# RUMBA_TFT.net
KiCad netlist of a schematic drawn in Altium Designer
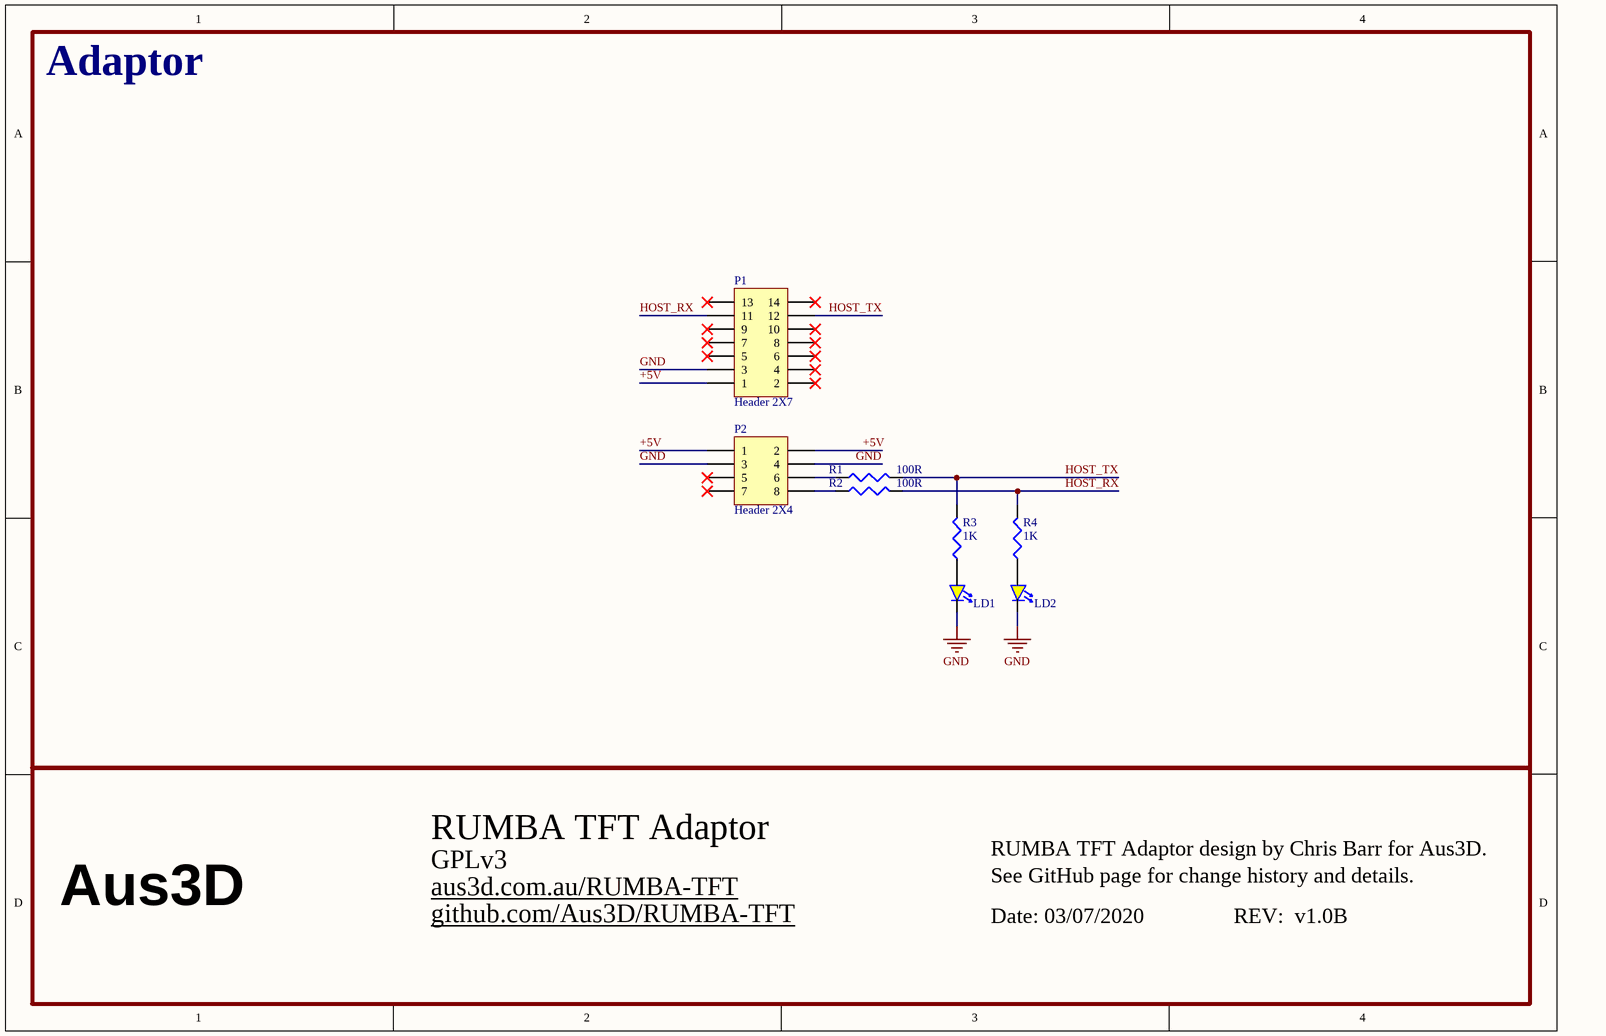
[diagram p0: RUMBA_TFT.SchDoc]

(export (version "E")
  (design (tool "Eeschema 10.0.6"))
  (components
    (comp (ref "LD1")
      (value "~")
      (footprint "LED 1608-0603")
      (description "LED YELLOW CLEAR CHIP SMD 0603")
      (libsource (lib "picoprint_library") (part "LEDY  0603"))
    )
    (comp (ref "LD2")
      (value "~")
      (footprint "LED 1608-0603")
      (description "LED YELLOW CLEAR CHIP SMD 0603")
      (libsource (lib "picoprint_library") (part "LEDY  0603"))
    )
    (comp (ref "P1")
      (value "Header 2X7")
      (footprint "HDR2X7-HEADER FEMALE")
      (description "Header, 7-Pin, Dual row, Female")
      (libsource (lib "main_library") (part "Header 2X7 Female"))
    )
    (comp (ref "P2")
      (value "Header 2X4")
      (footprint "HDR2X4-HEADER FEMALE - SHROUDED")
      (description "Header, 4-Pin, Dual row, Shrouded")
      (libsource (lib "main_library") (part "Header 2X4"))
    )
    (comp (ref "R1")
      (value "100R")
      (footprint "RES 1608-0603")
      (description "RES SMD 100 OHM 1% 1/10W 0603")
      (fields
        (field (name "TOLERANCE") "±1%")
        (field (name "Comment") "Resistor")
        (field (name "PUBLISHER") "Altium Limited")
      )
      (libsource (lib "Database_Libs1") (part "Resistor"))
    )
    (comp (ref "R2")
      (value "100R")
      (footprint "RES 1608-0603")
      (description "RES SMD 100 OHM 1% 1/10W 0603")
      (fields
        (field (name "TOLERANCE") "±1%")
        (field (name "Comment") "Resistor")
        (field (name "PUBLISHER") "Altium Limited")
      )
      (libsource (lib "Database_Libs1") (part "Resistor"))
    )
    (comp (ref "R3")
      (value "1K")
      (footprint "RES 1608-0603")
      (description "RES SMD 1K OHM 1% 1/10W 0603")
      (fields
        (field (name "TOLERANCE") "±1%")
        (field (name "Comment") "Resistor")
        (field (name "PUBLISHER") "Altium Limited")
      )
      (libsource (lib "Database_Libs1") (part "Resistor"))
    )
    (comp (ref "R4")
      (value "1K")
      (footprint "RES 1608-0603")
      (description "RES SMD 1K OHM 1% 1/10W 0603")
      (fields
        (field (name "TOLERANCE") "±1%")
        (field (name "Comment") "Resistor")
        (field (name "PUBLISHER") "Altium Limited")
      )
      (libsource (lib "Database_Libs1") (part "Resistor"))
    )
  )
  (nets
    (net (code "1") (name "/+5V") (class "Default")
      (node (ref "P1") (pin "1") (pinfunction "1_1") (pintype "passive"))
      (node (ref "P2") (pin "1") (pinfunction "1_1") (pintype "passive"))
      (node (ref "P2") (pin "2") (pinfunction "2_2") (pintype "passive"))
    )
    (net (code "2") (name "/HOST_RX") (class "Default")
      (node (ref "P1") (pin "11") (pinfunction "11_11") (pintype "passive"))
      (node (ref "R2") (pin "2") (pinfunction "2_2") (pintype "passive"))
      (node (ref "R4") (pin "2") (pinfunction "2_2") (pintype "passive"))
    )
    (net (code "3") (name "/HOST_TX") (class "Default")
      (node (ref "P1") (pin "12") (pinfunction "12_12") (pintype "passive"))
      (node (ref "R1") (pin "2") (pinfunction "2_2") (pintype "passive"))
      (node (ref "R3") (pin "2") (pinfunction "2_2") (pintype "passive"))
    )
    (net (code "4") (name "GND") (class "Default")
      (node (ref "LD1") (pin "2") (pinfunction "K_2") (pintype "passive"))
      (node (ref "LD2") (pin "2") (pinfunction "K_2") (pintype "passive"))
      (node (ref "P1") (pin "3") (pinfunction "3_3") (pintype "passive"))
      (node (ref "P2") (pin "3") (pinfunction "3_3") (pintype "passive"))
      (node (ref "P2") (pin "4") (pinfunction "4_4") (pintype "passive"))
    )
    (net (code "5") (name "Net-(LD1-A)") (class "Default")
      (node (ref "LD1") (pin "1") (pinfunction "A_1") (pintype "passive"))
      (node (ref "R3") (pin "1") (pinfunction "1_1") (pintype "passive"))
    )
    (net (code "6") (name "Net-(LD2-A)") (class "Default")
      (node (ref "LD2") (pin "1") (pinfunction "A_1") (pintype "passive"))
      (node (ref "R4") (pin "1") (pinfunction "1_1") (pintype "passive"))
    )
    (net (code "7") (name "Net-(P2-Pad6)") (class "Default")
      (node (ref "P2") (pin "6") (pinfunction "6_6") (pintype "passive"))
      (node (ref "R1") (pin "1") (pinfunction "1_1") (pintype "passive"))
    )
    (net (code "8") (name "Net-(P2-Pad8)") (class "Default")
      (node (ref "P2") (pin "8") (pinfunction "8_8") (pintype "passive"))
      (node (ref "R2") (pin "1") (pinfunction "1_1") (pintype "passive"))
    )
    (net (code "9") (name "unconnected-(P1-Pad2)") (class "Default")
      (node (ref "P1") (pin "2") (pinfunction "2_2") (pintype "passive+no_connect"))
    )
    (net (code "10") (name "unconnected-(P1-Pad4)") (class "Default")
      (node (ref "P1") (pin "4") (pinfunction "4_4") (pintype "passive+no_connect"))
    )
    (net (code "11") (name "unconnected-(P1-Pad5)") (class "Default")
      (node (ref "P1") (pin "5") (pinfunction "5_5") (pintype "passive+no_connect"))
    )
    (net (code "12") (name "unconnected-(P1-Pad6)") (class "Default")
      (node (ref "P1") (pin "6") (pinfunction "6_6") (pintype "passive+no_connect"))
    )
    (net (code "13") (name "unconnected-(P1-Pad7)") (class "Default")
      (node (ref "P1") (pin "7") (pinfunction "7_7") (pintype "passive+no_connect"))
    )
    (net (code "14") (name "unconnected-(P1-Pad8)") (class "Default")
      (node (ref "P1") (pin "8") (pinfunction "8_8") (pintype "passive+no_connect"))
    )
    (net (code "15") (name "unconnected-(P1-Pad9)") (class "Default")
      (node (ref "P1") (pin "9") (pinfunction "9_9") (pintype "passive+no_connect"))
    )
    (net (code "16") (name "unconnected-(P1-Pad10)") (class "Default")
      (node (ref "P1") (pin "10") (pinfunction "10_10") (pintype "passive+no_connect"))
    )
    (net (code "17") (name "unconnected-(P1-Pad13)") (class "Default")
      (node (ref "P1") (pin "13") (pinfunction "13_13") (pintype "passive+no_connect"))
    )
    (net (code "18") (name "unconnected-(P1-Pad14)") (class "Default")
      (node (ref "P1") (pin "14") (pinfunction "14_14") (pintype "passive+no_connect"))
    )
    (net (code "19") (name "unconnected-(P2-Pad5)") (class "Default")
      (node (ref "P2") (pin "5") (pinfunction "5_5") (pintype "passive+no_connect"))
    )
    (net (code "20") (name "unconnected-(P2-Pad7)") (class "Default")
      (node (ref "P2") (pin "7") (pinfunction "7_7") (pintype "passive+no_connect"))
    )
  )
)
